# MCU_USB.net
KiCad netlist of a schematic drawn in Altium Designer
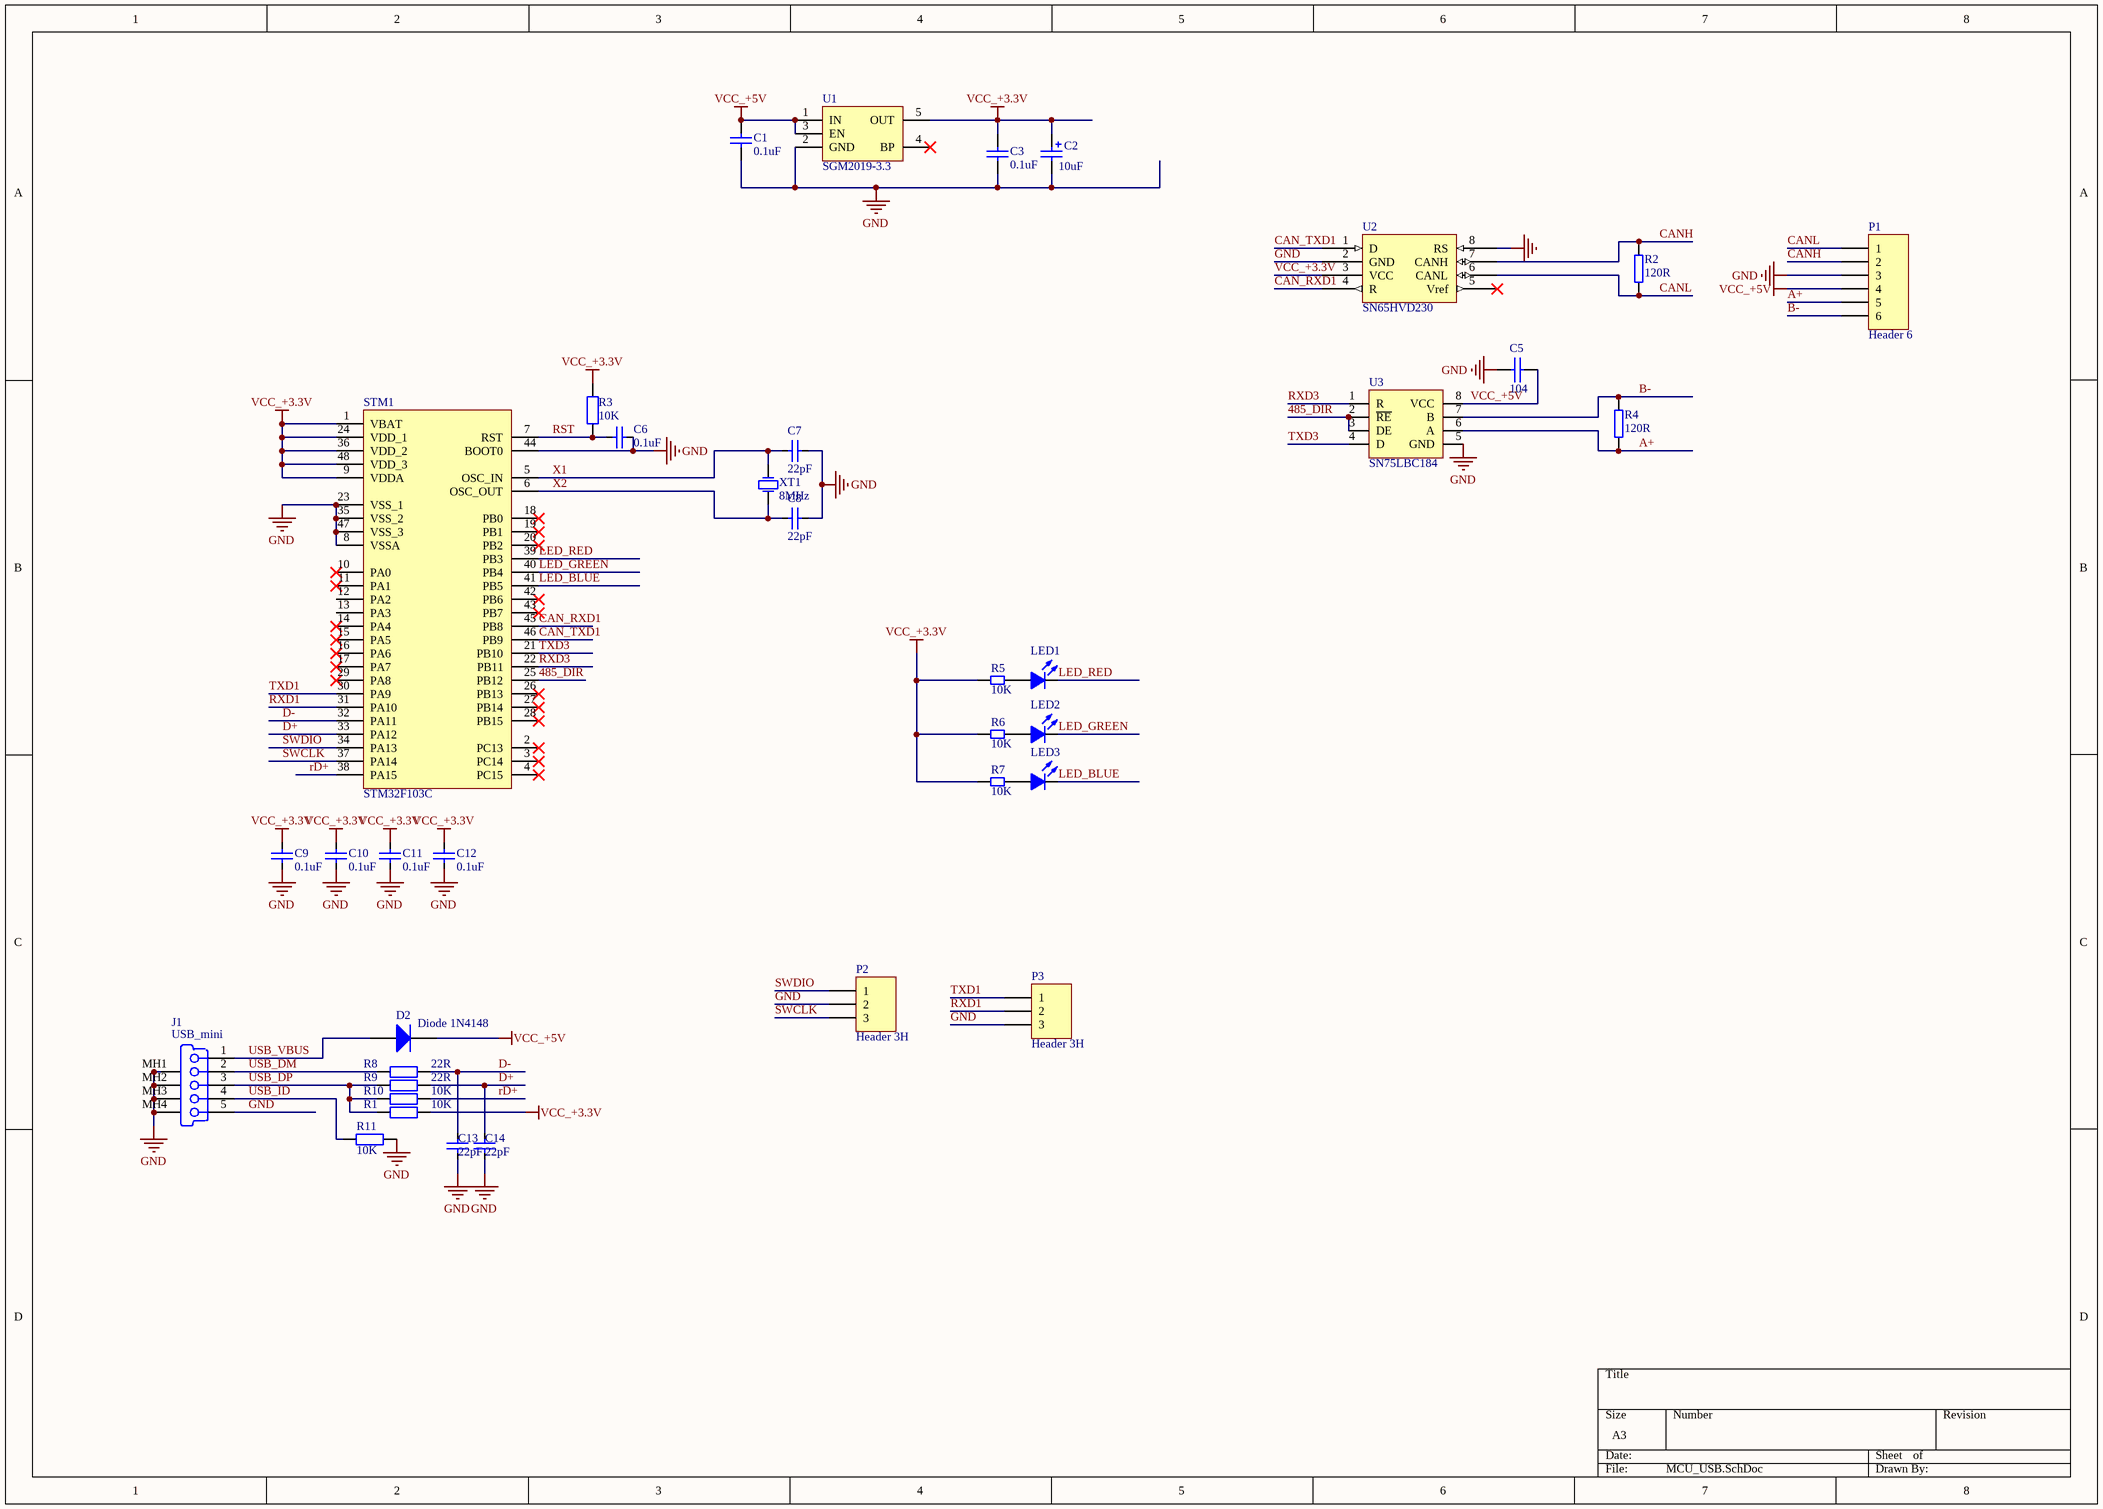
[diagram p0: MCU_USB.SchDoc]

(export (version "E")
  (design (tool "Eeschema 10.0.6"))
  (components
    (comp (ref "C1")
      (value "0.1uF")
      (footprint "0603C")
      (description "Capacitor")
      (fields (field (name "PUBLISHER") "Altium Limited"))
      (libsource (lib "Calf") (part "Cap"))
    )
    (comp (ref "C2")
      (value "10uF")
      (footprint "PcbLib:1812C")
      (description "Polarized Capacitor (Radial)")
      (fields (field (name "PUBLISHER") "Altium Limited"))
      (libsource (lib "Calf") (part "Cap Pol"))
    )
    (comp (ref "C3")
      (value "0.1uF")
      (footprint "0603C")
      (description "Capacitor")
      (fields (field (name "PUBLISHER") "Altium Limited"))
      (libsource (lib "Calf") (part "Cap"))
    )
    (comp (ref "C5") (value "104") (footprint "0603C") (libsource (lib "WT4815_CPU_Board") (part "0603C")))
    (comp (ref "C6")
      (value "0.1uF")
      (footprint "0603C")
      (description "Capacitor")
      (fields (field (name "Comment") "Cap_0603"))
      (libsource (lib "SCH_Passive") (part "0603C"))
    )
    (comp (ref "C7")
      (value "22pF")
      (footprint "0603C")
      (description "Capacitor")
      (fields (field (name "Comment") "Cap_0603"))
      (libsource (lib "SCH_Passive") (part "0603C"))
    )
    (comp (ref "C8")
      (value "22pF")
      (footprint "0603C")
      (description "Capacitor")
      (fields (field (name "Comment") "Cap_0603"))
      (libsource (lib "SCH_Passive") (part "0603C"))
    )
    (comp (ref "C9")
      (value "0.1uF")
      (footprint "0603C")
      (description "Capacitor")
      (fields (field (name "Comment") "Cap_0603"))
      (libsource (lib "SCH_Passive") (part "0603C"))
    )
    (comp (ref "C10")
      (value "0.1uF")
      (footprint "0603C")
      (description "Capacitor")
      (fields (field (name "Comment") "Cap_0603"))
      (libsource (lib "SCH_Passive") (part "0603C"))
    )
    (comp (ref "C11")
      (value "0.1uF")
      (footprint "0603C")
      (description "Capacitor")
      (fields (field (name "Comment") "Cap_0603"))
      (libsource (lib "SCH_Passive") (part "0603C"))
    )
    (comp (ref "C12")
      (value "0.1uF")
      (footprint "0603C")
      (description "Capacitor")
      (fields (field (name "Comment") "Cap_0603"))
      (libsource (lib "SCH_Passive") (part "0603C"))
    )
    (comp (ref "C13")
      (value "22pF")
      (footprint "0603C")
      (description "Capacitor")
      (fields (field (name "Comment") "Cap_0603"))
      (libsource (lib "SCH_Passive") (part "0603C"))
    )
    (comp (ref "C14")
      (value "22pF")
      (footprint "0603C")
      (description "Capacitor")
      (fields (field (name "Comment") "Cap_0603"))
      (libsource (lib "SCH_Passive") (part "0603C"))
    )
    (comp (ref "D2")
      (value "Diode 1N4148")
      (footprint "1206D")
      (description "High Conductance Fast Diode")
      (fields (field (name "PUBLISHER") "Altium Limited"))
      (libsource (lib "Miscellaneous Devices") (part "Diode 1N4148"))
    )
    (comp (ref "J1") (value "USB_mini") (footprint "USB") (libsource (lib "*") (part "0481900001")))
    (comp (ref "LED1")
      (value "LED")
      (footprint "LED-0603")
      (description "Typical INFRARED GaAs LED")
      (fields (field (name "PUBLISHER") "Altium Limited"))
      (libsource (lib "Calf") (part "LED"))
    )
    (comp (ref "LED2")
      (value "LED")
      (footprint "LED-0603")
      (description "Typical INFRARED GaAs LED")
      (fields (field (name "PUBLISHER") "Altium Limited"))
      (libsource (lib "Calf") (part "LED"))
    )
    (comp (ref "LED3")
      (value "LED")
      (footprint "LED-0603")
      (description "Typical INFRARED GaAs LED")
      (fields (field (name "PUBLISHER") "Altium Limited"))
      (libsource (lib "Calf") (part "LED"))
    )
    (comp (ref "P1")
      (value "Header 6")
      (footprint "HDR1X6")
      (description "Header, 6-Pin")
      (fields (field (name "PUBLISHER") "Altium Limited"))
      (libsource (lib "Miscellaneous Connectors") (part "Header 6"))
    )
    (comp (ref "P2")
      (value "Header 3H")
      (footprint "SIP3B")
      (description "Header, 3-Pin, Right Angle")
      (fields (field (name "PUBLISHER") "Altium Limited"))
      (libsource (lib "Miscellaneous Connectors") (part "Header 3H"))
    )
    (comp (ref "P3")
      (value "Header 3H")
      (footprint "SIP3B")
      (description "Header, 3-Pin, Right Angle")
      (fields (field (name "PUBLISHER") "Altium Limited"))
      (libsource (lib "Miscellaneous Connectors") (part "Header 3H"))
    )
    (comp (ref "R1")
      (value "10K")
      (footprint "0603R")
      (description "Resistor")
      (fields (field (name "Comment") "Res_0603"))
      (libsource (lib "") (part "0603R_1"))
    )
    (comp (ref "R2") (value "120R") (footprint "0603R") (libsource (lib "OBDII_CUBE") (part "RES2A")))
    (comp (ref "R3")
      (value "10K")
      (footprint "0603R")
      (description "Resistor")
      (fields (field (name "Comment") "Res_0603"))
      (libsource (lib "") (part "0603R_2"))
    )
    (comp (ref "R4") (value "120R") (footprint "0603R") (libsource (lib "OBDII_CUBE") (part "RES2A")))
    (comp (ref "R5")
      (value "10K")
      (footprint "0603R")
      (description "Resistor")
      (fields (field (name "PUBLISHER") "Altium Limited"))
      (libsource (lib "Calf") (part "Res2"))
    )
    (comp (ref "R6")
      (value "10K")
      (footprint "0603R")
      (description "Resistor")
      (fields (field (name "PUBLISHER") "Altium Limited"))
      (libsource (lib "Calf") (part "Res2"))
    )
    (comp (ref "R7")
      (value "10K")
      (footprint "0603R")
      (description "Resistor")
      (fields (field (name "PUBLISHER") "Altium Limited"))
      (libsource (lib "Calf") (part "Res2"))
    )
    (comp (ref "R8")
      (value "22R")
      (footprint "0603R")
      (description "Resistor")
      (fields (field (name "Comment") "Res_0603"))
      (libsource (lib "SCH_Passive") (part "0603R"))
    )
    (comp (ref "R9")
      (value "22R")
      (footprint "0603R")
      (description "Resistor")
      (fields (field (name "Comment") "Res_0603"))
      (libsource (lib "SCH_Passive") (part "0603R"))
    )
    (comp (ref "R10")
      (value "10K")
      (footprint "0603R")
      (description "Resistor")
      (fields (field (name "Comment") "Res_0603"))
      (libsource (lib "") (part "0603R_1"))
    )
    (comp (ref "R11")
      (value "10K")
      (footprint "0603R")
      (description "Resistor")
      (fields (field (name "Comment") "Res_0603"))
      (libsource (lib "SCH_Passive") (part "0603R"))
    )
    (comp (ref "STM1")
      (value "STM32F103C")
      (footprint "STM32F_48")
      (description "MCU")
      (libsource (lib "SCH_IC") (part "STM32F103C"))
    )
    (comp (ref "U1")
      (value "SGM2019-3.3")
      (footprint "SOT23-5")
      (libsource (lib "OBDII_CUBE") (part "SGM2019"))
    )
    (comp (ref "U2")
      (value "SN65HVD230")
      (footprint "SOP8")
      (libsource (lib "STR910_SCHLIB") (part "SN65HVD230D"))
    )
    (comp (ref "U3")
      (value "SN75LBC184")
      (footprint "SOP8")
      (libsource (lib "LPC2148Mobus") (part "SN75LBC184"))
    )
    (comp (ref "XT1")
      (value "8MHz")
      (footprint "5032SMD")
      (description "Crystal Oscillator")
      (fields (field (name "Comment") "XTAL_5032") (field (name "PUBLISHER") "Altium Limited"))
      (libsource (lib "SCH_Oscillator") (part "XTAL_5032"))
    )
  )
  (nets
    (net (code "1") (name "/485_DIR") (class "Default")
      (node (ref "STM1") (pin "25") (pinfunction "PB12_25") (pintype "passive"))
      (node (ref "U3") (pin "2") (pinfunction "~{RE}_2") (pintype "passive"))
      (node (ref "U3") (pin "3") (pinfunction "DE_3") (pintype "passive"))
    )
    (net (code "2") (name "/A+") (class "Default")
      (node (ref "P1") (pin "5") (pinfunction "5_5") (pintype "passive"))
      (node (ref "R4") (pin "2") (pintype "passive"))
      (node (ref "U3") (pin "6") (pinfunction "A_6") (pintype "passive"))
    )
    (net (code "3") (name "/B-") (class "Default")
      (node (ref "P1") (pin "6") (pinfunction "6_6") (pintype "passive"))
      (node (ref "R4") (pin "1") (pintype "passive"))
      (node (ref "U3") (pin "7") (pinfunction "B_7") (pintype "passive"))
    )
    (net (code "4") (name "/CANH") (class "Default")
      (node (ref "P1") (pin "2") (pinfunction "2_2") (pintype "passive"))
      (node (ref "R2") (pin "1") (pintype "passive"))
      (node (ref "U2") (pin "7") (pinfunction "CANH_7") (pintype "bidirectional"))
    )
    (net (code "5") (name "/CANL") (class "Default")
      (node (ref "P1") (pin "1") (pinfunction "1_1") (pintype "passive"))
      (node (ref "R2") (pin "2") (pintype "passive"))
      (node (ref "U2") (pin "6") (pinfunction "CANL_6") (pintype "bidirectional"))
    )
    (net (code "6") (name "/CAN_RXD1") (class "Default")
      (node (ref "STM1") (pin "45") (pinfunction "PB8_45") (pintype "passive"))
      (node (ref "U2") (pin "4") (pinfunction "R_4") (pintype "output"))
    )
    (net (code "7") (name "/CAN_TXD1") (class "Default")
      (node (ref "STM1") (pin "46") (pinfunction "PB9_46") (pintype "passive"))
      (node (ref "U2") (pin "1") (pinfunction "D_1") (pintype "input"))
    )
    (net (code "8") (name "/D+") (class "Default")
      (node (ref "C14") (pin "1") (pinfunction "1_1") (pintype "passive"))
      (node (ref "R9") (pin "1") (pinfunction "1_1") (pintype "passive"))
      (node (ref "STM1") (pin "33") (pinfunction "PA12_33") (pintype "passive"))
    )
    (net (code "9") (name "/D-") (class "Default")
      (node (ref "C13") (pin "1") (pinfunction "1_1") (pintype "passive"))
      (node (ref "R8") (pin "1") (pinfunction "1_1") (pintype "passive"))
      (node (ref "STM1") (pin "32") (pinfunction "PA11_32") (pintype "passive"))
    )
    (net (code "10") (name "/LED_BLUE") (class "Default")
      (node (ref "LED3") (pin "2") (pinfunction "K_2") (pintype "passive"))
      (node (ref "STM1") (pin "41") (pinfunction "PB5_41") (pintype "passive"))
    )
    (net (code "11") (name "/LED_GREEN") (class "Default")
      (node (ref "LED2") (pin "2") (pinfunction "K_2") (pintype "passive"))
      (node (ref "STM1") (pin "40") (pinfunction "PB4_40") (pintype "passive"))
    )
    (net (code "12") (name "/LED_RED") (class "Default")
      (node (ref "LED1") (pin "2") (pinfunction "K_2") (pintype "passive"))
      (node (ref "STM1") (pin "39") (pinfunction "PB3_39") (pintype "passive"))
    )
    (net (code "13") (name "/RST") (class "Default")
      (node (ref "C6") (pin "2") (pinfunction "2_2") (pintype "passive"))
      (node (ref "R3") (pin "2") (pinfunction "2_2") (pintype "passive"))
      (node (ref "STM1") (pin "7") (pinfunction "RST_7") (pintype "passive"))
    )
    (net (code "14") (name "/RXD1") (class "Default")
      (node (ref "P3") (pin "2") (pinfunction "2_2") (pintype "passive"))
      (node (ref "STM1") (pin "31") (pinfunction "PA10_31") (pintype "passive"))
    )
    (net (code "15") (name "/RXD3") (class "Default")
      (node (ref "STM1") (pin "22") (pinfunction "PB11_22") (pintype "passive"))
      (node (ref "U3") (pin "1") (pinfunction "R_1") (pintype "passive"))
    )
    (net (code "16") (name "/SWCLK") (class "Default")
      (node (ref "P2") (pin "3") (pinfunction "3_3") (pintype "passive"))
      (node (ref "STM1") (pin "37") (pinfunction "PA14_37") (pintype "passive"))
    )
    (net (code "17") (name "/SWDIO") (class "Default")
      (node (ref "P2") (pin "1") (pinfunction "1_1") (pintype "passive"))
      (node (ref "STM1") (pin "34") (pinfunction "PA13_34") (pintype "passive"))
    )
    (net (code "18") (name "/TXD1") (class "Default")
      (node (ref "P3") (pin "1") (pinfunction "1_1") (pintype "passive"))
      (node (ref "STM1") (pin "30") (pinfunction "PA9_30") (pintype "passive"))
    )
    (net (code "19") (name "/TXD3") (class "Default")
      (node (ref "STM1") (pin "21") (pinfunction "PB10_21") (pintype "passive"))
      (node (ref "U3") (pin "4") (pinfunction "D_4") (pintype "passive"))
    )
    (net (code "20") (name "/USB_DM") (class "Default")
      (node (ref "J1") (pin "2") (pinfunction "D-_2") (pintype "passive"))
      (node (ref "R8") (pin "2") (pinfunction "2_2") (pintype "passive"))
    )
    (net (code "21") (name "/USB_DP") (class "Default")
      (node (ref "J1") (pin "3") (pinfunction "D+_3") (pintype "passive"))
      (node (ref "R1") (pin "1") (pinfunction "1_1") (pintype "passive"))
      (node (ref "R10") (pin "1") (pinfunction "1_1") (pintype "passive"))
      (node (ref "R9") (pin "2") (pinfunction "2_2") (pintype "passive"))
    )
    (net (code "22") (name "/USB_ID") (class "Default")
      (node (ref "J1") (pin "4") (pinfunction "NC_4") (pintype "passive"))
      (node (ref "R11") (pin "2") (pinfunction "2_2") (pintype "passive"))
    )
    (net (code "23") (name "/USB_VBUS") (class "Default")
      (node (ref "D2") (pin "1") (pinfunction "A_1") (pintype "passive"))
      (node (ref "J1") (pin "1") (pinfunction "V_BUS_(5V)_1") (pintype "passive"))
    )
    (net (code "24") (name "/X1") (class "Default")
      (node (ref "C7") (pin "2") (pinfunction "2_2") (pintype "passive"))
      (node (ref "STM1") (pin "5") (pinfunction "OSC_IN_5") (pintype "passive"))
      (node (ref "XT1") (pin "1") (pinfunction "OSC1_1") (pintype "passive"))
    )
    (net (code "25") (name "/X2") (class "Default")
      (node (ref "C8") (pin "2") (pinfunction "2_2") (pintype "passive"))
      (node (ref "STM1") (pin "6") (pinfunction "OSC_OUT_6") (pintype "passive"))
      (node (ref "XT1") (pin "2") (pinfunction "OSC2_2") (pintype "passive"))
    )
    (net (code "26") (name "/rD+") (class "Default")
      (node (ref "R10") (pin "2") (pinfunction "2_2") (pintype "passive"))
      (node (ref "STM1") (pin "38") (pinfunction "PA15_38") (pintype "passive"))
    )
    (net (code "27") (name "GND") (class "Default")
      (node (ref "C1") (pin "1") (pinfunction "1_1") (pintype "passive"))
      (node (ref "C10") (pin "1") (pinfunction "1_1") (pintype "passive"))
      (node (ref "C11") (pin "1") (pinfunction "1_1") (pintype "passive"))
      (node (ref "C12") (pin "1") (pinfunction "1_1") (pintype "passive"))
      (node (ref "C13") (pin "2") (pinfunction "2_2") (pintype "passive"))
      (node (ref "C14") (pin "2") (pinfunction "2_2") (pintype "passive"))
      (node (ref "C2") (pin "2") (pinfunction "2_2") (pintype "passive"))
      (node (ref "C3") (pin "1") (pinfunction "1_1") (pintype "passive"))
      (node (ref "C5") (pin "1") (pintype "passive"))
      (node (ref "C6") (pin "1") (pinfunction "1_1") (pintype "passive"))
      (node (ref "C7") (pin "1") (pinfunction "1_1") (pintype "passive"))
      (node (ref "C8") (pin "1") (pinfunction "1_1") (pintype "passive"))
      (node (ref "C9") (pin "1") (pinfunction "1_1") (pintype "passive"))
      (node (ref "J1") (pin "5") (pinfunction "GND_5") (pintype "passive"))
      (node (ref "J1") (pin "MH1") (pinfunction "Tab_MH1") (pintype "passive"))
      (node (ref "J1") (pin "MH2") (pinfunction "Tab_MH2") (pintype "passive"))
      (node (ref "J1") (pin "MH3") (pinfunction "Tab_MH3") (pintype "passive"))
      (node (ref "J1") (pin "MH4") (pinfunction "Tab_MH4") (pintype "passive"))
      (node (ref "P1") (pin "3") (pinfunction "3_3") (pintype "passive"))
      (node (ref "P2") (pin "2") (pinfunction "2_2") (pintype "passive"))
      (node (ref "P3") (pin "3") (pinfunction "3_3") (pintype "passive"))
      (node (ref "R11") (pin "1") (pinfunction "1_1") (pintype "passive"))
      (node (ref "STM1") (pin "23") (pinfunction "VSS_1_23") (pintype "passive"))
      (node (ref "STM1") (pin "35") (pinfunction "VSS_2_35") (pintype "passive"))
      (node (ref "STM1") (pin "44") (pinfunction "BOOT0_44") (pintype "passive"))
      (node (ref "STM1") (pin "47") (pinfunction "VSS_3_47") (pintype "passive"))
      (node (ref "STM1") (pin "8") (pinfunction "VSSA_8") (pintype "passive"))
      (node (ref "U1") (pin "2") (pinfunction "GND_2") (pintype "passive"))
      (node (ref "U2") (pin "2") (pinfunction "GND_2") (pintype "power_in"))
      (node (ref "U2") (pin "8") (pinfunction "RS_8") (pintype "input"))
      (node (ref "U3") (pin "5") (pinfunction "GND_5") (pintype "passive"))
    )
    (net (code "28") (name "Net-(LED1-A)") (class "Default")
      (node (ref "LED1") (pin "1") (pinfunction "A_1") (pintype "passive"))
      (node (ref "R5") (pin "2") (pinfunction "2_2") (pintype "passive"))
    )
    (net (code "29") (name "Net-(LED2-A)") (class "Default")
      (node (ref "LED2") (pin "1") (pinfunction "A_1") (pintype "passive"))
      (node (ref "R6") (pin "2") (pinfunction "2_2") (pintype "passive"))
    )
    (net (code "30") (name "Net-(LED3-A)") (class "Default")
      (node (ref "LED3") (pin "1") (pinfunction "A_1") (pintype "passive"))
      (node (ref "R7") (pin "2") (pinfunction "2_2") (pintype "passive"))
    )
    (net (code "31") (name "VCC_+3.3V") (class "Default")
      (node (ref "C10") (pin "2") (pinfunction "2_2") (pintype "passive"))
      (node (ref "C11") (pin "2") (pinfunction "2_2") (pintype "passive"))
      (node (ref "C12") (pin "2") (pinfunction "2_2") (pintype "passive"))
      (node (ref "C2") (pin "1") (pinfunction "1_1") (pintype "passive"))
      (node (ref "C3") (pin "2") (pinfunction "2_2") (pintype "passive"))
      (node (ref "C9") (pin "2") (pinfunction "2_2") (pintype "passive"))
      (node (ref "R1") (pin "2") (pinfunction "2_2") (pintype "passive"))
      (node (ref "R3") (pin "1") (pinfunction "1_1") (pintype "passive"))
      (node (ref "R5") (pin "1") (pinfunction "1_1") (pintype "passive"))
      (node (ref "R6") (pin "1") (pinfunction "1_1") (pintype "passive"))
      (node (ref "R7") (pin "1") (pinfunction "1_1") (pintype "passive"))
      (node (ref "STM1") (pin "1") (pinfunction "VBAT_1") (pintype "passive"))
      (node (ref "STM1") (pin "24") (pinfunction "VDD_1_24") (pintype "passive"))
      (node (ref "STM1") (pin "36") (pinfunction "VDD_2_36") (pintype "passive"))
      (node (ref "STM1") (pin "48") (pinfunction "VDD_3_48") (pintype "passive"))
      (node (ref "STM1") (pin "9") (pinfunction "VDDA_9") (pintype "passive"))
      (node (ref "U1") (pin "5") (pinfunction "OUT_5") (pintype "passive"))
      (node (ref "U2") (pin "3") (pinfunction "VCC_3") (pintype "power_in"))
    )
    (net (code "32") (name "VCC_+5V") (class "Default")
      (node (ref "C1") (pin "2") (pinfunction "2_2") (pintype "passive"))
      (node (ref "C5") (pin "2") (pintype "passive"))
      (node (ref "D2") (pin "2") (pinfunction "K_2") (pintype "passive"))
      (node (ref "P1") (pin "4") (pinfunction "4_4") (pintype "passive"))
      (node (ref "U1") (pin "1") (pinfunction "IN_1") (pintype "passive"))
      (node (ref "U1") (pin "3") (pinfunction "EN_3") (pintype "passive"))
      (node (ref "U3") (pin "8") (pinfunction "VCC_8") (pintype "passive"))
    )
    (net (code "33") (name "unconnected-(STM1-PA0-Pad10)") (class "Default")
      (node (ref "STM1") (pin "10") (pinfunction "PA0_10") (pintype "passive+no_connect"))
    )
    (net (code "34") (name "unconnected-(STM1-PA1-Pad11)") (class "Default")
      (node (ref "STM1") (pin "11") (pinfunction "PA1_11") (pintype "passive+no_connect"))
    )
    (net (code "35") (name "unconnected-(STM1-PA2-Pad12)") (class "Default")
      (node (ref "STM1") (pin "12") (pinfunction "PA2_12") (pintype "passive"))
    )
    (net (code "36") (name "unconnected-(STM1-PA3-Pad13)") (class "Default")
      (node (ref "STM1") (pin "13") (pinfunction "PA3_13") (pintype "passive"))
    )
    (net (code "37") (name "unconnected-(STM1-PA4-Pad14)") (class "Default")
      (node (ref "STM1") (pin "14") (pinfunction "PA4_14") (pintype "passive+no_connect"))
    )
    (net (code "38") (name "unconnected-(STM1-PA5-Pad15)") (class "Default")
      (node (ref "STM1") (pin "15") (pinfunction "PA5_15") (pintype "passive+no_connect"))
    )
    (net (code "39") (name "unconnected-(STM1-PA6-Pad16)") (class "Default")
      (node (ref "STM1") (pin "16") (pinfunction "PA6_16") (pintype "passive+no_connect"))
    )
    (net (code "40") (name "unconnected-(STM1-PA7-Pad17)") (class "Default")
      (node (ref "STM1") (pin "17") (pinfunction "PA7_17") (pintype "passive+no_connect"))
    )
    (net (code "41") (name "unconnected-(STM1-PA8-Pad29)") (class "Default")
      (node (ref "STM1") (pin "29") (pinfunction "PA8_29") (pintype "passive+no_connect"))
    )
    (net (code "42") (name "unconnected-(STM1-PB0-Pad18)") (class "Default")
      (node (ref "STM1") (pin "18") (pinfunction "PB0_18") (pintype "passive+no_connect"))
    )
    (net (code "43") (name "unconnected-(STM1-PB1-Pad19)") (class "Default")
      (node (ref "STM1") (pin "19") (pinfunction "PB1_19") (pintype "passive+no_connect"))
    )
    (net (code "44") (name "unconnected-(STM1-PB2-Pad20)") (class "Default")
      (node (ref "STM1") (pin "20") (pinfunction "PB2_20") (pintype "passive+no_connect"))
    )
    (net (code "45") (name "unconnected-(STM1-PB6-Pad42)") (class "Default")
      (node (ref "STM1") (pin "42") (pinfunction "PB6_42") (pintype "passive+no_connect"))
    )
    (net (code "46") (name "unconnected-(STM1-PB7-Pad43)") (class "Default")
      (node (ref "STM1") (pin "43") (pinfunction "PB7_43") (pintype "passive+no_connect"))
    )
    (net (code "47") (name "unconnected-(STM1-PB13-Pad26)") (class "Default")
      (node (ref "STM1") (pin "26") (pinfunction "PB13_26") (pintype "passive+no_connect"))
    )
    (net (code "48") (name "unconnected-(STM1-PB14-Pad27)") (class "Default")
      (node (ref "STM1") (pin "27") (pinfunction "PB14_27") (pintype "passive+no_connect"))
    )
    (net (code "49") (name "unconnected-(STM1-PB15-Pad28)") (class "Default")
      (node (ref "STM1") (pin "28") (pinfunction "PB15_28") (pintype "passive+no_connect"))
    )
    (net (code "50") (name "unconnected-(STM1-PC13-Pad2)") (class "Default")
      (node (ref "STM1") (pin "2") (pinfunction "PC13_2") (pintype "passive+no_connect"))
    )
    (net (code "51") (name "unconnected-(STM1-PC14-Pad3)") (class "Default")
      (node (ref "STM1") (pin "3") (pinfunction "PC14_3") (pintype "passive+no_connect"))
    )
    (net (code "52") (name "unconnected-(STM1-PC15-Pad4)") (class "Default")
      (node (ref "STM1") (pin "4") (pinfunction "PC15_4") (pintype "passive+no_connect"))
    )
    (net (code "53") (name "unconnected-(U1-BP-Pad4)") (class "Default")
      (node (ref "U1") (pin "4") (pinfunction "BP_4") (pintype "passive+no_connect"))
    )
    (net (code "54") (name "unconnected-(U2-Vref-Pad5)") (class "Default")
      (node (ref "U2") (pin "5") (pinfunction "Vref_5") (pintype "output+no_connect"))
    )
  )
)
